# rcstick-f-small.net
KiCad netlist of a schematic drawn in EAGLE
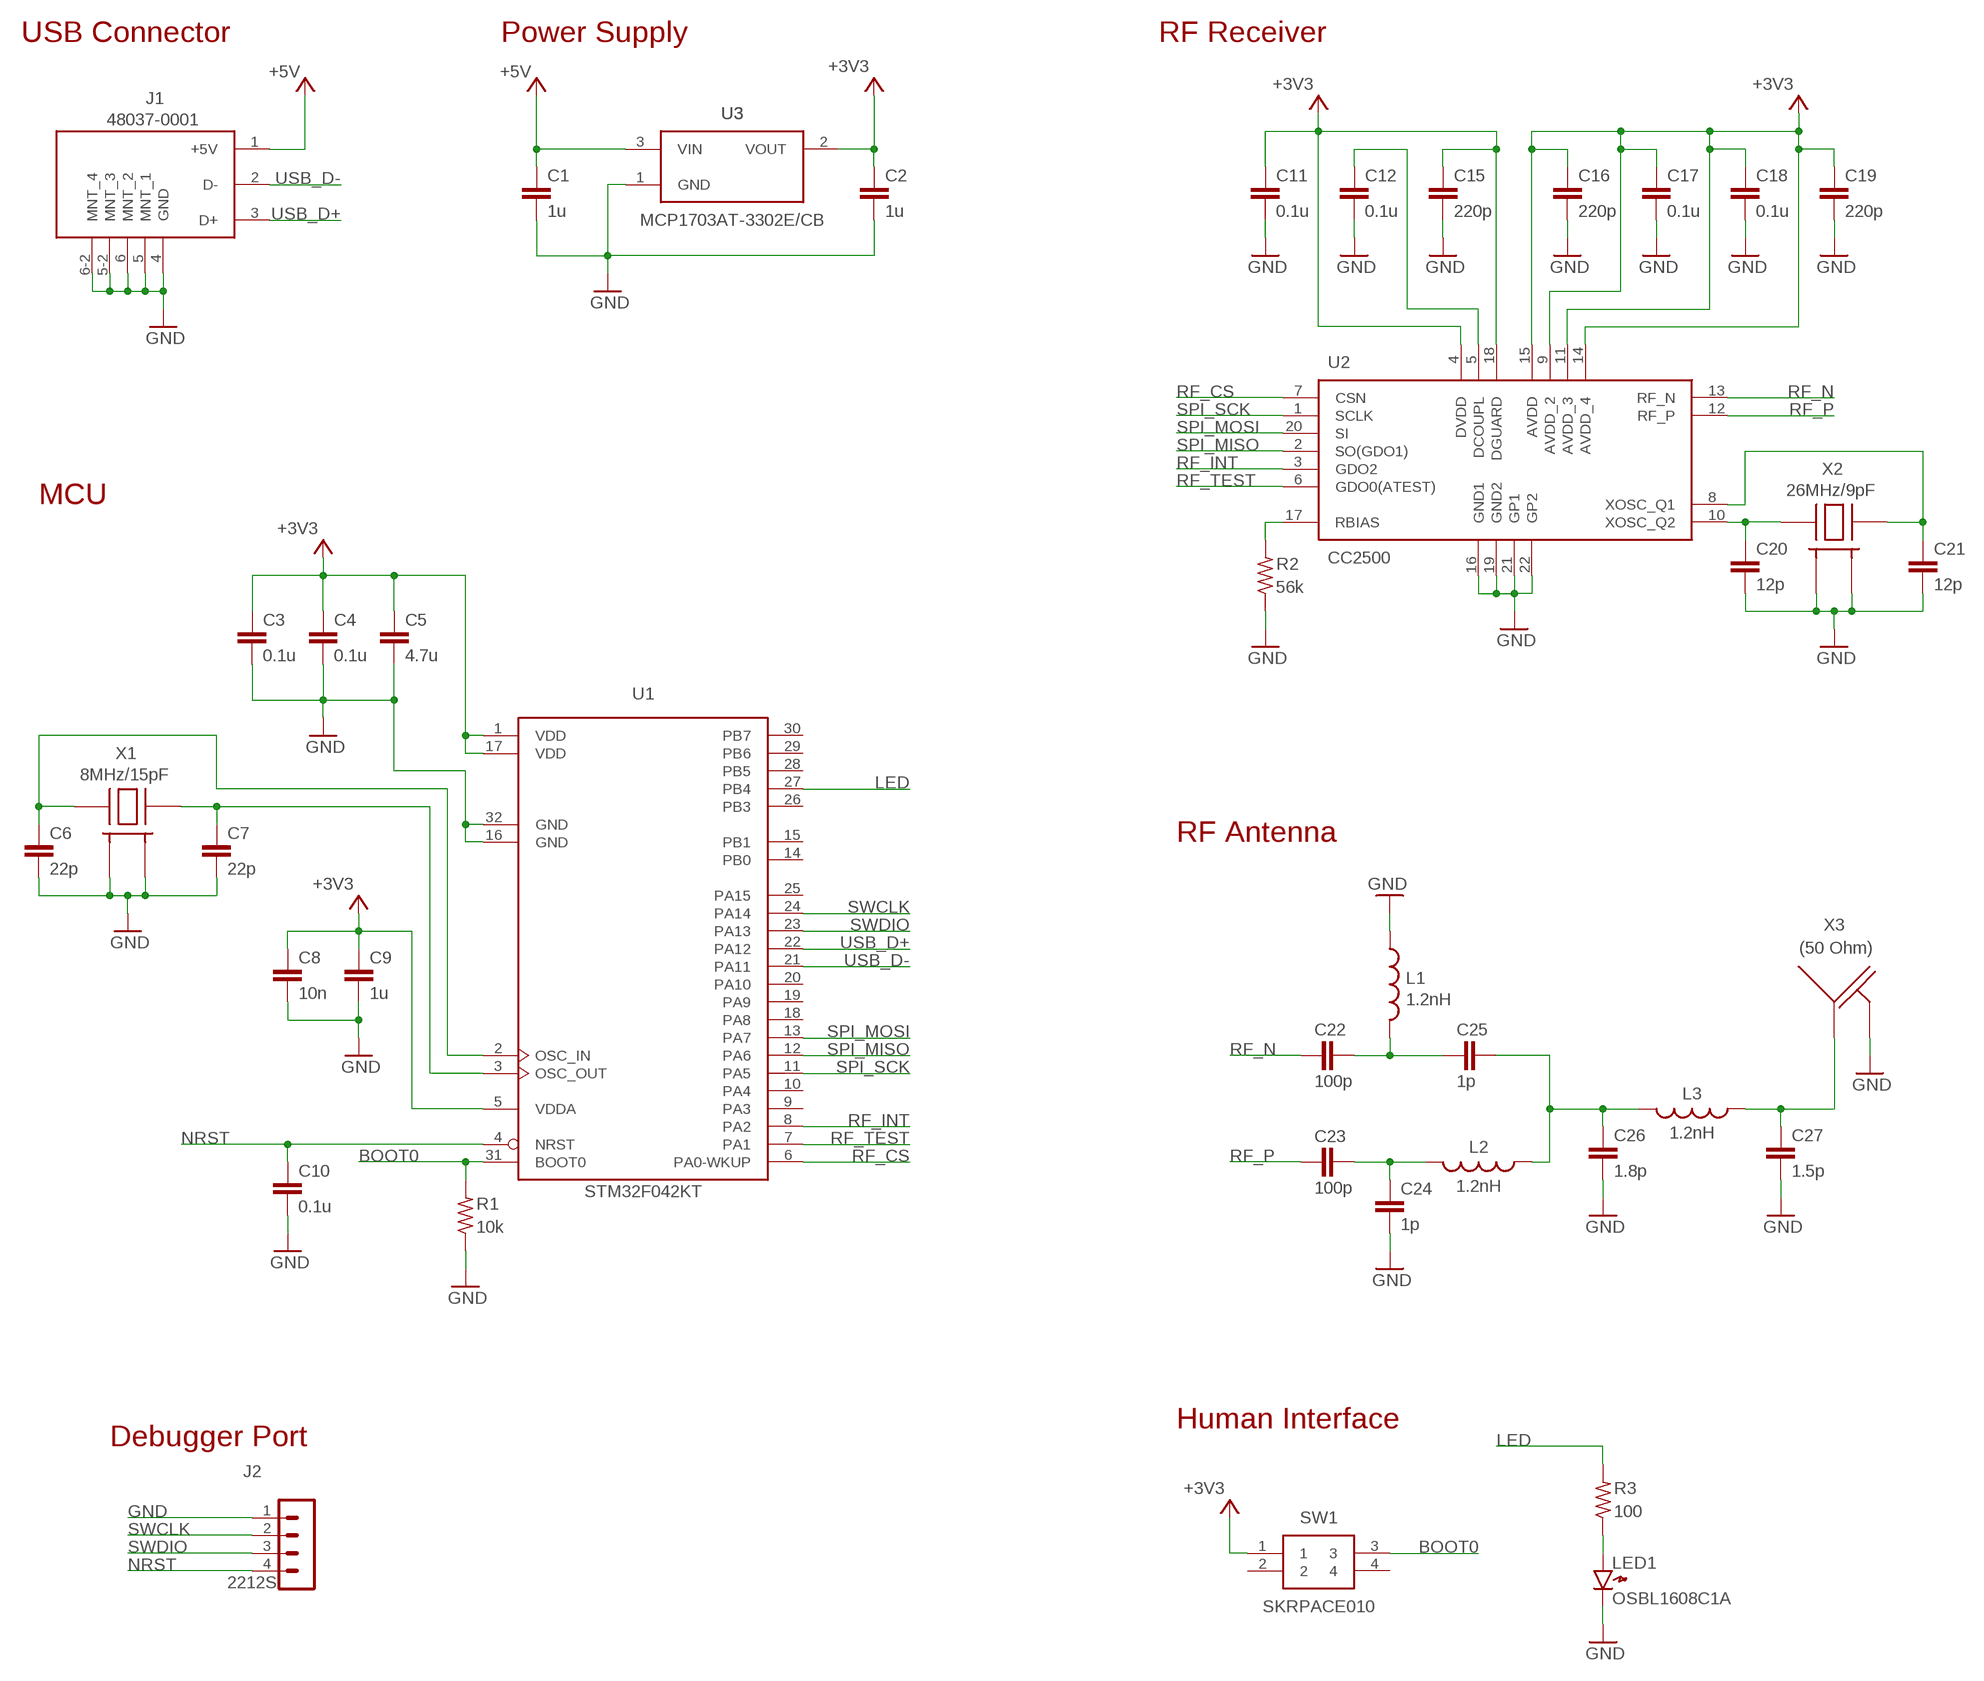
[diagram p0: schematic, sheet 1]

(export (version "E")
  (design (tool "Eeschema 10.0.6"))
  (components
    (comp (ref "C1")
      (value "1u")
      (footprint "eagle-import:RCL_C0402_HS")
      (libsource (lib "eagle-import") (part "RCL_C-EUC0402-HS"))
    )
    (comp (ref "C2")
      (value "1u")
      (footprint "eagle-import:RCL_C0402_HS")
      (libsource (lib "eagle-import") (part "RCL_C-EUC0402-HS"))
    )
    (comp (ref "C3")
      (value "0.1u")
      (footprint "eagle-import:RCL_C0402_HS")
      (libsource (lib "eagle-import") (part "RCL_C-EUC0402-HS"))
    )
    (comp (ref "C4")
      (value "0.1u")
      (footprint "eagle-import:RCL_C0402_HS")
      (libsource (lib "eagle-import") (part "RCL_C-EUC0402-HS"))
    )
    (comp (ref "C5")
      (value "4.7u")
      (footprint "eagle-import:RCL_C0402_HS")
      (libsource (lib "eagle-import") (part "RCL_C-EUC0402-HS"))
    )
    (comp (ref "C6")
      (value "22p")
      (footprint "eagle-import:RCL_C0402_HS")
      (libsource (lib "eagle-import") (part "RCL_C-EUC0402-HS"))
    )
    (comp (ref "C7")
      (value "22p")
      (footprint "eagle-import:RCL_C0402_HS")
      (libsource (lib "eagle-import") (part "RCL_C-EUC0402-HS"))
    )
    (comp (ref "C8")
      (value "10n")
      (footprint "eagle-import:RCL_C0402_HS")
      (libsource (lib "eagle-import") (part "RCL_C-EUC0402-HS"))
    )
    (comp (ref "C9")
      (value "1u")
      (footprint "eagle-import:RCL_C0402_HS")
      (libsource (lib "eagle-import") (part "RCL_C-EUC0402-HS"))
    )
    (comp (ref "C10")
      (value "0.1u")
      (footprint "eagle-import:RCL_C0402_HS")
      (libsource (lib "eagle-import") (part "RCL_C-EUC0402-HS"))
    )
    (comp (ref "C11")
      (value "0.1u")
      (footprint "eagle-import:RCL_C0402_HS")
      (libsource (lib "eagle-import") (part "RCL_C-EUC0402-HS"))
    )
    (comp (ref "C12")
      (value "0.1u")
      (footprint "eagle-import:RCL_C0402_HS")
      (libsource (lib "eagle-import") (part "RCL_C-EUC0402-HS"))
    )
    (comp (ref "C15")
      (value "220p")
      (footprint "eagle-import:RCL_C0402_HS")
      (libsource (lib "eagle-import") (part "RCL_C-EUC0402-HS"))
    )
    (comp (ref "C16")
      (value "220p")
      (footprint "eagle-import:RCL_C0402_HS")
      (libsource (lib "eagle-import") (part "RCL_C-EUC0402-HS"))
    )
    (comp (ref "C17")
      (value "0.1u")
      (footprint "eagle-import:RCL_C0402_HS")
      (libsource (lib "eagle-import") (part "RCL_C-EUC0402-HS"))
    )
    (comp (ref "C18")
      (value "0.1u")
      (footprint "eagle-import:RCL_C0402_HS")
      (libsource (lib "eagle-import") (part "RCL_C-EUC0402-HS"))
    )
    (comp (ref "C19")
      (value "220p")
      (footprint "eagle-import:RCL_C0402_HS")
      (libsource (lib "eagle-import") (part "RCL_C-EUC0402-HS"))
    )
    (comp (ref "C20")
      (value "12p")
      (footprint "eagle-import:RCL_C0402_HS")
      (libsource (lib "eagle-import") (part "RCL_C-EUC0402-HS"))
    )
    (comp (ref "C21")
      (value "12p")
      (footprint "eagle-import:RCL_C0402_HS")
      (libsource (lib "eagle-import") (part "RCL_C-EUC0402-HS"))
    )
    (comp (ref "C22")
      (value "100p")
      (footprint "eagle-import:RCL_C0402_HS")
      (libsource (lib "eagle-import") (part "RCL_C-EUC0402-HS"))
    )
    (comp (ref "C23")
      (value "100p")
      (footprint "eagle-import:RCL_C0402_HS")
      (libsource (lib "eagle-import") (part "RCL_C-EUC0402-HS"))
    )
    (comp (ref "C24")
      (value "1p")
      (footprint "eagle-import:RCL_C0402_HS")
      (libsource (lib "eagle-import") (part "RCL_C-EUC0402-HS"))
    )
    (comp (ref "C25")
      (value "1p")
      (footprint "eagle-import:RCL_C0402_HS")
      (libsource (lib "eagle-import") (part "RCL_C-EUC0402-HS"))
    )
    (comp (ref "C26")
      (value "1.8p")
      (footprint "eagle-import:RCL_C0402_HS")
      (libsource (lib "eagle-import") (part "RCL_C-EUC0402-HS"))
    )
    (comp (ref "C27")
      (value "1.5p")
      (footprint "eagle-import:RCL_C0402_HS")
      (libsource (lib "eagle-import") (part "RCL_C-EUC0402-HS"))
    )
    (comp (ref "J1")
      (value "MOLEX_48037-0001")
      (footprint "eagle-import:MOLEX_48037-0001_1")
      (libsource (lib "eagle-import") (part "MOLEX_48037-0001"))
    )
    (comp (ref "J2")
      (value "2212S")
      (footprint "eagle-import:53047-0410")
      (libsource (lib "eagle-import") (part "53047-0410"))
    )
    (comp (ref "L1")
      (value "1.2nH")
      (footprint "eagle-import:RCL_L0402_HS")
      (libsource (lib "eagle-import") (part "RCL_L-USL0402-HS"))
    )
    (comp (ref "L2")
      (value "1.2nH")
      (footprint "eagle-import:RCL_L0402_HS")
      (libsource (lib "eagle-import") (part "RCL_L-USL0402-HS"))
    )
    (comp (ref "L3")
      (value "1.2nH")
      (footprint "eagle-import:RCL_L0402_HS")
      (libsource (lib "eagle-import") (part "RCL_L-USL0402-HS"))
    )
    (comp (ref "LED1")
      (value "OSBL1608C1A")
      (footprint "eagle-import:LED1608")
      (libsource (lib "eagle-import") (part "LED1608"))
    )
    (comp (ref "R1")
      (value "10k")
      (footprint "eagle-import:RCL_R0402_HS")
      (libsource (lib "eagle-import") (part "RCL_R-US_R0402-HS"))
    )
    (comp (ref "R2")
      (value "56k")
      (footprint "eagle-import:RCL_R0402_HS")
      (libsource (lib "eagle-import") (part "RCL_R-US_R0402-HS"))
    )
    (comp (ref "R3")
      (value "100")
      (footprint "eagle-import:RCL_R0402_HS")
      (libsource (lib "eagle-import") (part "RCL_R-US_R0402-HS"))
    )
    (comp (ref "SW1")
      (value "SKRPACE010")
      (footprint "eagle-import:SMT(4.2X3.2)")
      (libsource (lib "eagle-import") (part "SKRPACE010"))
    )
    (comp (ref "U1")
      (value "STM32F042KT")
      (footprint "eagle-import:LQFP32-M")
      (libsource (lib "eagle-import") (part "STM32F042KT"))
    )
    (comp (ref "U2")
      (value "CC2500")
      (footprint "eagle-import:CC2500-RTY1_CC2500-HS")
      (libsource (lib "eagle-import") (part "CC2500-HS"))
    )
    (comp (ref "U3")
      (value "MCP1703AT-3302E/CB")
      (footprint "eagle-import:SOT23")
      (libsource (lib "eagle-import") (part "LDO-REGULATOR"))
    )
    (comp (ref "X1")
      (value "8MHz/15pF")
      (footprint "eagle-import:CRYSTAL3225-HS")
      (libsource (lib "eagle-import") (part "CRYSTAL3225HS"))
    )
    (comp (ref "X2")
      (value "26MHz/9pF")
      (footprint "eagle-import:CRYSTAL3225-HS")
      (libsource (lib "eagle-import") (part "CRYSTAL3225HS"))
    )
    (comp (ref "X3")
      (value "(50 Ohm)")
      (footprint "eagle-import:2.4GHZ-INVERTED-F-SMALL-FLIP")
      (libsource (lib "eagle-import") (part "2.4GHZ-INVERED-FSMALL-FLIP"))
    )
  )
  (nets
    (net (code "1") (name "+3V3") (class "Default")
      (node (ref "C11") (pin "1") (pinfunction "1_1") (pintype "passive"))
      (node (ref "C15") (pin "1") (pinfunction "1_1") (pintype "passive"))
      (node (ref "C16") (pin "1") (pinfunction "1_1") (pintype "passive"))
      (node (ref "C17") (pin "1") (pinfunction "1_1") (pintype "passive"))
      (node (ref "C18") (pin "1") (pinfunction "1_1") (pintype "passive"))
      (node (ref "C19") (pin "1") (pinfunction "1_1") (pintype "passive"))
      (node (ref "C2") (pin "1") (pinfunction "1_1") (pintype "passive"))
      (node (ref "C3") (pin "1") (pinfunction "1_1") (pintype "passive"))
      (node (ref "C4") (pin "1") (pinfunction "1_1") (pintype "passive"))
      (node (ref "C5") (pin "1") (pinfunction "1_1") (pintype "passive"))
      (node (ref "C8") (pin "1") (pinfunction "1_1") (pintype "passive"))
      (node (ref "C9") (pin "1") (pinfunction "1_1") (pintype "passive"))
      (node (ref "SW1") (pin "1") (pinfunction "1_1") (pintype "bidirectional"))
      (node (ref "U1") (pin "1") (pinfunction "VDD_1") (pintype "power_in"))
      (node (ref "U1") (pin "17") (pinfunction "VDD_17") (pintype "power_in"))
      (node (ref "U1") (pin "5") (pinfunction "VDDA_5") (pintype "power_in"))
      (node (ref "U2") (pin "11") (pinfunction "AVDD_3_11") (pintype "bidirectional"))
      (node (ref "U2") (pin "14") (pinfunction "AVDD_4_14") (pintype "bidirectional"))
      (node (ref "U2") (pin "15") (pinfunction "AVDD_15") (pintype "bidirectional"))
      (node (ref "U2") (pin "18") (pinfunction "DGUARD_18") (pintype "bidirectional"))
      (node (ref "U2") (pin "4") (pinfunction "DVDD_4") (pintype "bidirectional"))
      (node (ref "U2") (pin "9") (pinfunction "AVDD_2_9") (pintype "bidirectional"))
      (node (ref "U3") (pin "2") (pinfunction "VOUT_2") (pintype "bidirectional"))
    )
    (net (code "2") (name "+5V") (class "Default")
      (node (ref "C1") (pin "1") (pinfunction "1_1") (pintype "passive"))
      (node (ref "J1") (pin "1") (pinfunction "+5V_1") (pintype "bidirectional"))
      (node (ref "U3") (pin "3") (pinfunction "VIN_3") (pintype "bidirectional"))
    )
    (net (code "3") (name "/BOOT0") (class "Default")
      (node (ref "R1") (pin "2") (pinfunction "2_2") (pintype "passive"))
      (node (ref "SW1") (pin "3") (pinfunction "3_3") (pintype "bidirectional"))
      (node (ref "U1") (pin "31") (pinfunction "BOOT0_31") (pintype "input"))
    )
    (net (code "4") (name "/LED") (class "Default")
      (node (ref "R3") (pin "2") (pinfunction "2_2") (pintype "passive"))
      (node (ref "U1") (pin "27") (pinfunction "PB4_27") (pintype "bidirectional"))
    )
    (net (code "5") (name "/NRST") (class "Default")
      (node (ref "C10") (pin "1") (pinfunction "1_1") (pintype "passive"))
      (node (ref "J2") (pin "4") (pinfunction "4_4") (pintype "passive"))
      (node (ref "U1") (pin "4") (pinfunction "NRST_4") (pintype "bidirectional"))
    )
    (net (code "6") (name "/RF_CS") (class "Default")
      (node (ref "U1") (pin "6") (pinfunction "PA0-WKUP_6") (pintype "bidirectional"))
      (node (ref "U2") (pin "7") (pinfunction "CSN_7") (pintype "bidirectional"))
    )
    (net (code "7") (name "/RF_INT") (class "Default")
      (node (ref "U1") (pin "8") (pinfunction "PA2_8") (pintype "bidirectional"))
      (node (ref "U2") (pin "3") (pinfunction "GDO2_3") (pintype "bidirectional"))
    )
    (net (code "8") (name "/RF_N") (class "Default")
      (node (ref "C22") (pin "1") (pinfunction "1_1") (pintype "passive"))
      (node (ref "U2") (pin "13") (pinfunction "RF_N_13") (pintype "bidirectional"))
    )
    (net (code "9") (name "/RF_P") (class "Default")
      (node (ref "C23") (pin "1") (pinfunction "1_1") (pintype "passive"))
      (node (ref "U2") (pin "12") (pinfunction "RF_P_12") (pintype "bidirectional"))
    )
    (net (code "10") (name "/RF_TEST") (class "Default")
      (node (ref "U1") (pin "7") (pinfunction "PA1_7") (pintype "bidirectional"))
      (node (ref "U2") (pin "6") (pinfunction "GDO0(ATEST)_6") (pintype "bidirectional"))
    )
    (net (code "11") (name "/SPI_MISO") (class "Default")
      (node (ref "U1") (pin "12") (pinfunction "PA6_12") (pintype "bidirectional"))
      (node (ref "U2") (pin "2") (pinfunction "SO(GDO1)_2") (pintype "bidirectional"))
    )
    (net (code "12") (name "/SPI_MOSI") (class "Default")
      (node (ref "U1") (pin "13") (pinfunction "PA7_13") (pintype "bidirectional"))
      (node (ref "U2") (pin "20") (pinfunction "SI_20") (pintype "bidirectional"))
    )
    (net (code "13") (name "/SPI_SCK") (class "Default")
      (node (ref "U1") (pin "11") (pinfunction "PA5_11") (pintype "bidirectional"))
      (node (ref "U2") (pin "1") (pinfunction "SCLK_1") (pintype "bidirectional"))
    )
    (net (code "14") (name "/SWCLK") (class "Default")
      (node (ref "J2") (pin "2") (pinfunction "2_2") (pintype "passive"))
      (node (ref "U1") (pin "24") (pinfunction "PA14_24") (pintype "bidirectional"))
    )
    (net (code "15") (name "/SWDIO") (class "Default")
      (node (ref "J2") (pin "3") (pinfunction "3_3") (pintype "passive"))
      (node (ref "U1") (pin "23") (pinfunction "PA13_23") (pintype "bidirectional"))
    )
    (net (code "16") (name "/USB_D+") (class "Default")
      (node (ref "J1") (pin "3") (pinfunction "D+_3") (pintype "bidirectional"))
      (node (ref "U1") (pin "22") (pinfunction "PA12_22") (pintype "bidirectional"))
    )
    (net (code "17") (name "/USB_D-") (class "Default")
      (node (ref "J1") (pin "2") (pinfunction "D-_2") (pintype "bidirectional"))
      (node (ref "U1") (pin "21") (pinfunction "PA11_21") (pintype "bidirectional"))
    )
    (net (code "18") (name "GND") (class "Default")
      (node (ref "C1") (pin "2") (pinfunction "2_2") (pintype "passive"))
      (node (ref "C10") (pin "2") (pinfunction "2_2") (pintype "passive"))
      (node (ref "C11") (pin "2") (pinfunction "2_2") (pintype "passive"))
      (node (ref "C12") (pin "2") (pinfunction "2_2") (pintype "passive"))
      (node (ref "C15") (pin "2") (pinfunction "2_2") (pintype "passive"))
      (node (ref "C16") (pin "2") (pinfunction "2_2") (pintype "passive"))
      (node (ref "C17") (pin "2") (pinfunction "2_2") (pintype "passive"))
      (node (ref "C18") (pin "2") (pinfunction "2_2") (pintype "passive"))
      (node (ref "C19") (pin "2") (pinfunction "2_2") (pintype "passive"))
      (node (ref "C2") (pin "2") (pinfunction "2_2") (pintype "passive"))
      (node (ref "C20") (pin "2") (pinfunction "2_2") (pintype "passive"))
      (node (ref "C21") (pin "2") (pinfunction "2_2") (pintype "passive"))
      (node (ref "C24") (pin "2") (pinfunction "2_2") (pintype "passive"))
      (node (ref "C26") (pin "2") (pinfunction "2_2") (pintype "passive"))
      (node (ref "C27") (pin "2") (pinfunction "2_2") (pintype "passive"))
      (node (ref "C3") (pin "2") (pinfunction "2_2") (pintype "passive"))
      (node (ref "C4") (pin "2") (pinfunction "2_2") (pintype "passive"))
      (node (ref "C5") (pin "2") (pinfunction "2_2") (pintype "passive"))
      (node (ref "C6") (pin "2") (pinfunction "2_2") (pintype "passive"))
      (node (ref "C7") (pin "2") (pinfunction "2_2") (pintype "passive"))
      (node (ref "C8") (pin "2") (pinfunction "2_2") (pintype "passive"))
      (node (ref "C9") (pin "2") (pinfunction "2_2") (pintype "passive"))
      (node (ref "J1") (pin "4") (pinfunction "GND_4") (pintype "bidirectional"))
      (node (ref "J1") (pin "5") (pinfunction "MNT_1_5") (pintype "bidirectional"))
      (node (ref "J1") (pin "5-2") (pinfunction "MNT_3_5-2") (pintype "bidirectional"))
      (node (ref "J1") (pin "6") (pinfunction "MNT_2_6") (pintype "bidirectional"))
      (node (ref "J1") (pin "6-2") (pinfunction "MNT_4_6-2") (pintype "bidirectional"))
      (node (ref "J2") (pin "1") (pinfunction "1_1") (pintype "passive"))
      (node (ref "L1") (pin "1") (pinfunction "1_1") (pintype "passive"))
      (node (ref "LED1") (pin "K") (pinfunction "K_K") (pintype "passive"))
      (node (ref "R1") (pin "1") (pinfunction "1_1") (pintype "passive"))
      (node (ref "R2") (pin "1") (pinfunction "1_1") (pintype "passive"))
      (node (ref "U1") (pin "16") (pinfunction "GND_16") (pintype "power_in"))
      (node (ref "U1") (pin "32") (pinfunction "GND_32") (pintype "power_in"))
      (node (ref "U2") (pin "16") (pinfunction "GND1_16") (pintype "bidirectional"))
      (node (ref "U2") (pin "19") (pinfunction "GND2_19") (pintype "bidirectional"))
      (node (ref "U2") (pin "21") (pinfunction "GP1_21") (pintype "bidirectional"))
      (node (ref "U2") (pin "22") (pinfunction "GP2_22") (pintype "bidirectional"))
      (node (ref "U3") (pin "1") (pinfunction "GND_1") (pintype "bidirectional"))
      (node (ref "X1") (pin "2") (pinfunction "GND_1_2") (pintype "bidirectional"))
      (node (ref "X1") (pin "4") (pinfunction "GND_2_4") (pintype "bidirectional"))
      (node (ref "X2") (pin "2") (pinfunction "GND_1_2") (pintype "bidirectional"))
      (node (ref "X2") (pin "4") (pinfunction "GND_2_4") (pintype "bidirectional"))
      (node (ref "X3") (pin "2") (pinfunction "GND_2") (pintype "bidirectional"))
    )
    (net (code "19") (name "Net-(C22-Pad2)") (class "Default")
      (node (ref "C22") (pin "2") (pinfunction "2_2") (pintype "passive"))
      (node (ref "C25") (pin "1") (pinfunction "1_1") (pintype "passive"))
      (node (ref "L1") (pin "2") (pinfunction "2_2") (pintype "passive"))
    )
    (net (code "20") (name "Net-(C23-Pad2)") (class "Default")
      (node (ref "C23") (pin "2") (pinfunction "2_2") (pintype "passive"))
      (node (ref "C24") (pin "1") (pinfunction "1_1") (pintype "passive"))
      (node (ref "L2") (pin "2") (pinfunction "2_2") (pintype "passive"))
    )
    (net (code "21") (name "Net-(C25-Pad2)") (class "Default")
      (node (ref "C25") (pin "2") (pinfunction "2_2") (pintype "passive"))
      (node (ref "C26") (pin "1") (pinfunction "1_1") (pintype "passive"))
      (node (ref "L2") (pin "1") (pinfunction "1_1") (pintype "passive"))
      (node (ref "L3") (pin "2") (pinfunction "2_2") (pintype "passive"))
    )
    (net (code "22") (name "Net-(LED1-PadA)") (class "Default")
      (node (ref "LED1") (pin "A") (pinfunction "A_A") (pintype "passive"))
      (node (ref "R3") (pin "1") (pinfunction "1_1") (pintype "passive"))
    )
    (net (code "23") (name "Net-(U1-OSC_IN)") (class "Default")
      (node (ref "C6") (pin "1") (pinfunction "1_1") (pintype "passive"))
      (node (ref "U1") (pin "2") (pinfunction "OSC_IN_2") (pintype "bidirectional"))
      (node (ref "X1") (pin "1") (pinfunction "HOT_1_1") (pintype "bidirectional"))
    )
    (net (code "24") (name "Net-(U1-OSC_OUT)") (class "Default")
      (node (ref "C7") (pin "1") (pinfunction "1_1") (pintype "passive"))
      (node (ref "U1") (pin "3") (pinfunction "OSC_OUT_3") (pintype "bidirectional"))
      (node (ref "X1") (pin "3") (pinfunction "HOT_2_3") (pintype "bidirectional"))
    )
    (net (code "25") (name "Net-(U2-DCOUPL)") (class "Default")
      (node (ref "C12") (pin "1") (pinfunction "1_1") (pintype "passive"))
      (node (ref "U2") (pin "5") (pinfunction "DCOUPL_5") (pintype "bidirectional"))
    )
    (net (code "26") (name "Net-(U2-RBIAS)") (class "Default")
      (node (ref "R2") (pin "2") (pinfunction "2_2") (pintype "passive"))
      (node (ref "U2") (pin "17") (pinfunction "RBIAS_17") (pintype "bidirectional"))
    )
    (net (code "27") (name "Net-(U2-XOSC_Q1)") (class "Default")
      (node (ref "C21") (pin "1") (pinfunction "1_1") (pintype "passive"))
      (node (ref "U2") (pin "8") (pinfunction "XOSC_Q1_8") (pintype "bidirectional"))
      (node (ref "X2") (pin "3") (pinfunction "HOT_2_3") (pintype "bidirectional"))
    )
    (net (code "28") (name "Net-(U2-XOSC_Q2)") (class "Default")
      (node (ref "C20") (pin "1") (pinfunction "1_1") (pintype "passive"))
      (node (ref "U2") (pin "10") (pinfunction "XOSC_Q2_10") (pintype "bidirectional"))
      (node (ref "X2") (pin "1") (pinfunction "HOT_1_1") (pintype "bidirectional"))
    )
    (net (code "29") (name "Net-(X3-ANT)") (class "Default")
      (node (ref "C27") (pin "1") (pinfunction "1_1") (pintype "passive"))
      (node (ref "L3") (pin "1") (pinfunction "1_1") (pintype "passive"))
      (node (ref "X3") (pin "1") (pinfunction "ANT_1") (pintype "bidirectional"))
    )
    (net (code "30") (name "unconnected-(SW1-Pad2)") (class "Default")
      (node (ref "SW1") (pin "2") (pinfunction "2_2") (pintype "bidirectional"))
    )
    (net (code "31") (name "unconnected-(SW1-Pad4)") (class "Default")
      (node (ref "SW1") (pin "4") (pinfunction "4_4") (pintype "bidirectional"))
    )
    (net (code "32") (name "unconnected-(U1-PA3-Pad9)") (class "Default")
      (node (ref "U1") (pin "9") (pinfunction "PA3_9") (pintype "bidirectional"))
    )
    (net (code "33") (name "unconnected-(U1-PA4-Pad10)") (class "Default")
      (node (ref "U1") (pin "10") (pinfunction "PA4_10") (pintype "bidirectional"))
    )
    (net (code "34") (name "unconnected-(U1-PA8-Pad18)") (class "Default")
      (node (ref "U1") (pin "18") (pinfunction "PA8_18") (pintype "bidirectional"))
    )
    (net (code "35") (name "unconnected-(U1-PA9-Pad19)") (class "Default")
      (node (ref "U1") (pin "19") (pinfunction "PA9_19") (pintype "bidirectional"))
    )
    (net (code "36") (name "unconnected-(U1-PA10-Pad20)") (class "Default")
      (node (ref "U1") (pin "20") (pinfunction "PA10_20") (pintype "bidirectional"))
    )
    (net (code "37") (name "unconnected-(U1-PA15-Pad25)") (class "Default")
      (node (ref "U1") (pin "25") (pinfunction "PA15_25") (pintype "bidirectional"))
    )
    (net (code "38") (name "unconnected-(U1-PB0-Pad14)") (class "Default")
      (node (ref "U1") (pin "14") (pinfunction "PB0_14") (pintype "bidirectional"))
    )
    (net (code "39") (name "unconnected-(U1-PB1-Pad15)") (class "Default")
      (node (ref "U1") (pin "15") (pinfunction "PB1_15") (pintype "bidirectional"))
    )
    (net (code "40") (name "unconnected-(U1-PB3-Pad26)") (class "Default")
      (node (ref "U1") (pin "26") (pinfunction "PB3_26") (pintype "bidirectional"))
    )
    (net (code "41") (name "unconnected-(U1-PB5-Pad28)") (class "Default")
      (node (ref "U1") (pin "28") (pinfunction "PB5_28") (pintype "bidirectional"))
    )
    (net (code "42") (name "unconnected-(U1-PB6-Pad29)") (class "Default")
      (node (ref "U1") (pin "29") (pinfunction "PB6_29") (pintype "bidirectional"))
    )
    (net (code "43") (name "unconnected-(U1-PB7-Pad30)") (class "Default")
      (node (ref "U1") (pin "30") (pinfunction "PB7_30") (pintype "bidirectional"))
    )
  )
)
